# Main.net
KiCad netlist of a schematic drawn in Altium Designer
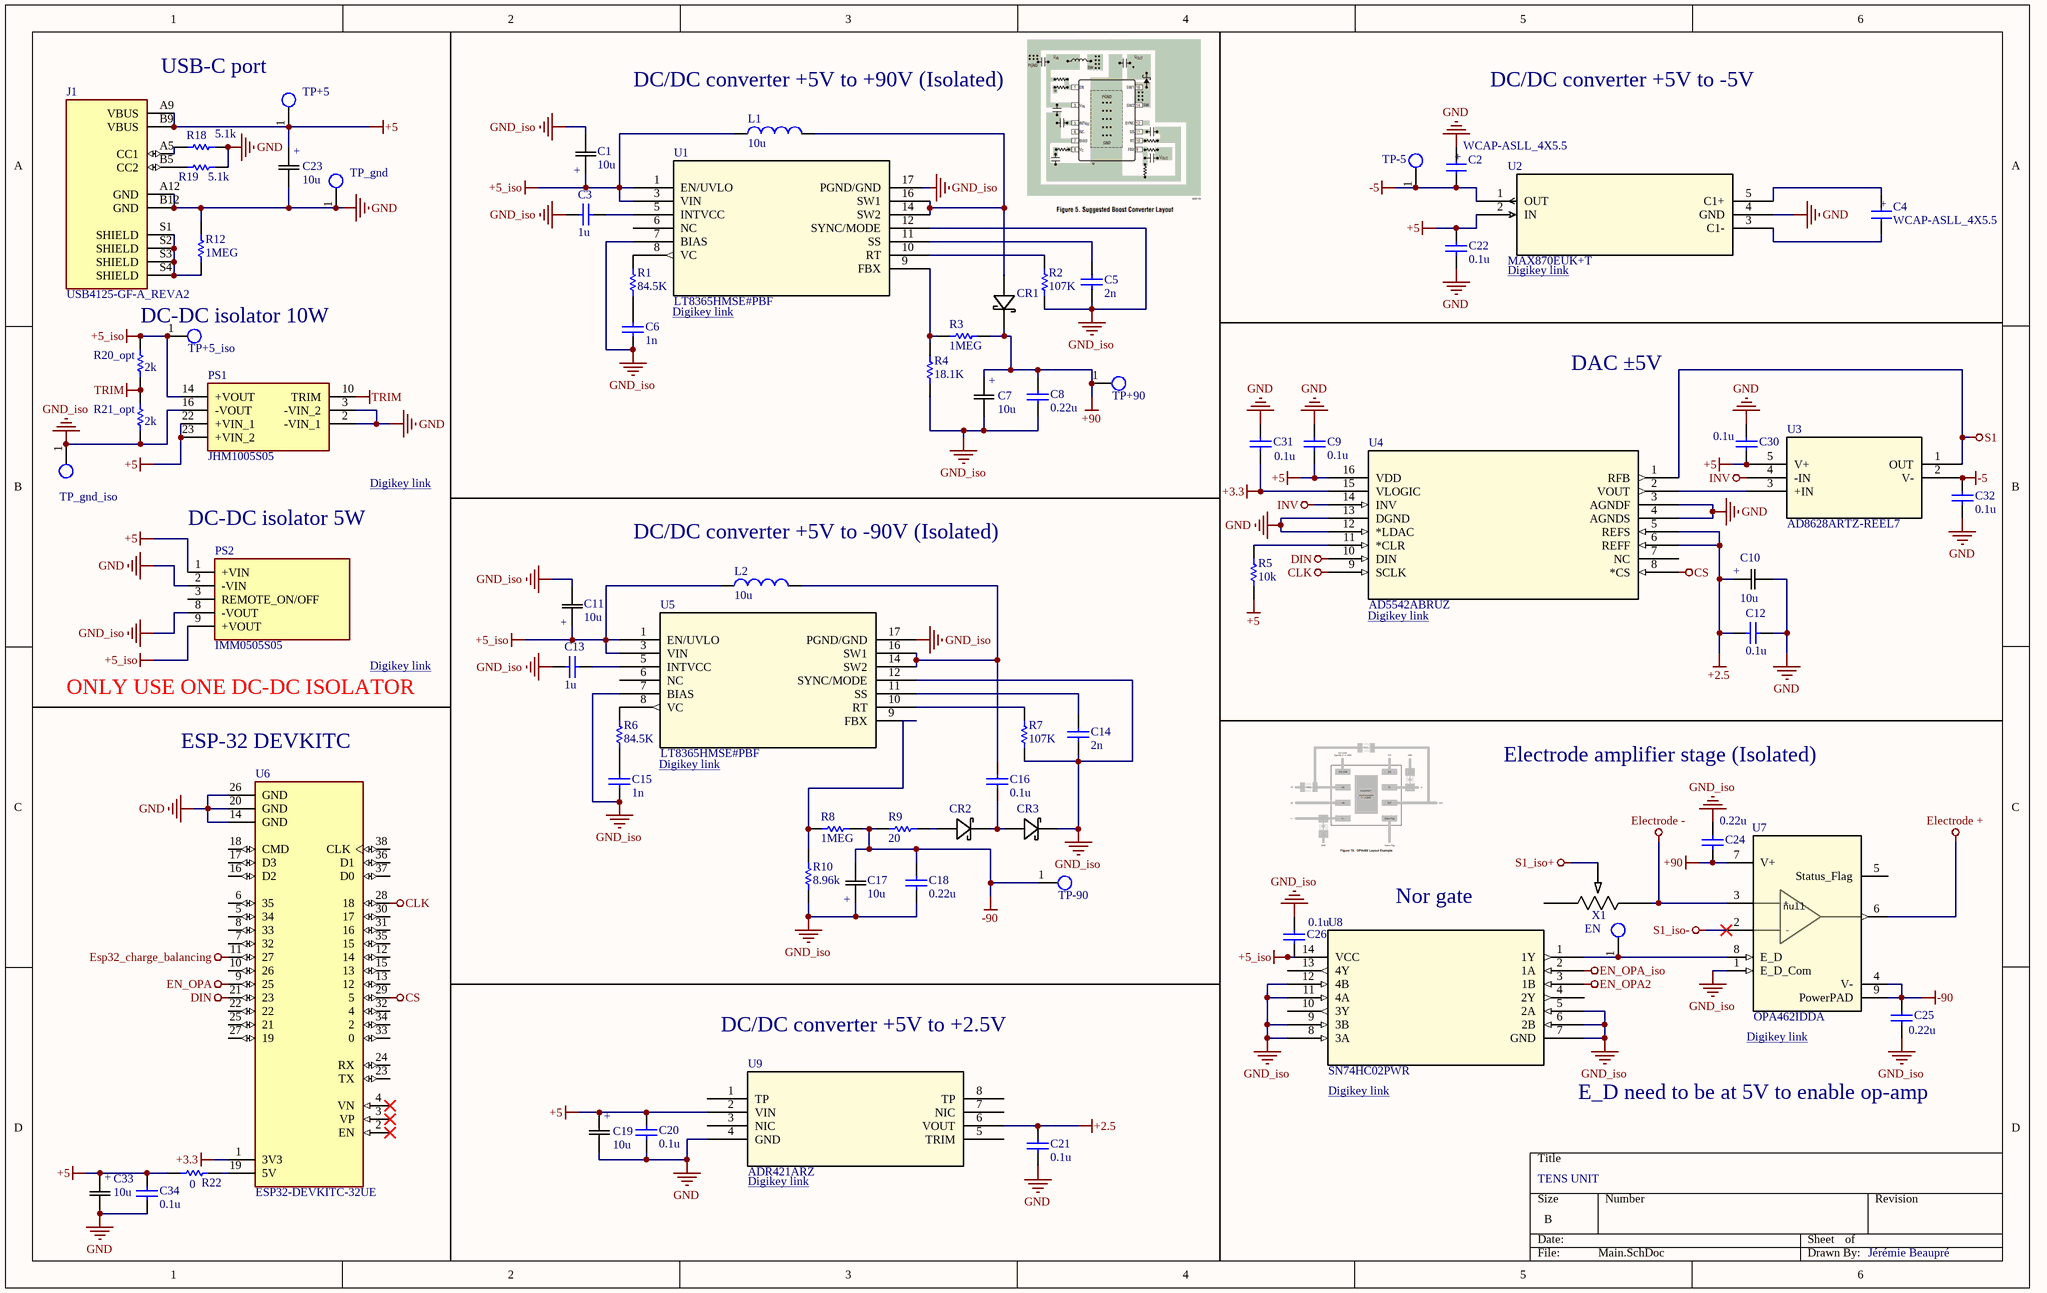
[diagram p0: Main.SchDoc]

(export (version "E")
  (design (tool "Eeschema 10.0.6"))
  (components
    (comp (ref "C1")
      (value "10u")
      (footprint "CAP_BX_10x20_RUB")
      (description "No Description Available")
      (fields
        (field (name "MANUFACTURER_PART_NUMBER") "450BXC10MEFC10X20")
        (field (name "COPYRIGHT") "Copyright (C) 2026 Ultra Librarian. All rights reserved.")
      )
      (libsource (lib "450BXC10MEFC10X20") (part "450BXC10MEFC10X20"))
    )
    (comp (ref "C2")
      (value "WCAP-ASLL_4X5.5")
      (footprint "WCAP-ASLL_4X5.5(DXL)")
      (fields
        (field (name "MF") "{'manufacturer': u'~{W}xfcrth Elektronik'}")
        (field (name "MP") "865060640001")
      )
      (libsource (lib "WCAP-ASLL_4X5.5") (part "WCAP-ASLL_4X5.5"))
    )
    (comp (ref "C3")
      (value "1u")
      (footprint "0805_AVX")
      (description "Capacitor")
      (libsource (lib "Simulation Generic Components") (part "Capacitor"))
    )
    (comp (ref "C4")
      (value "WCAP-ASLL_4X5.5")
      (footprint "WCAP-ASLL_4X5.5(DXL)")
      (fields
        (field (name "MF") "{'manufacturer': u'~{W}xfcrth Elektronik'}")
        (field (name "MP") "865060640001")
      )
      (libsource (lib "WCAP-ASLL_4X5.5") (part "WCAP-ASLL_4X5.5"))
    )
    (comp (ref "C5")
      (value "2n")
      (footprint "CAPC2012X75N")
      (description "Capacitor")
      (libsource (lib "Simulation Generic Components") (part "Capacitor"))
    )
    (comp (ref "C6")
      (value "1n")
      (footprint "CC0805N_YAG")
      (description "Capacitor")
      (libsource (lib "Simulation Generic Components") (part "Capacitor"))
    )
    (comp (ref "C7")
      (value "10u")
      (footprint "CAP_BX_10x20_RUB")
      (description "No Description Available")
      (fields
        (field (name "MANUFACTURER_PART_NUMBER") "450BXC10MEFC10X20")
        (field (name "COPYRIGHT") "Copyright (C) 2026 Ultra Librarian. All rights reserved.")
      )
      (libsource (lib "450BXC10MEFC10X20") (part "450BXC10MEFC10X20"))
    )
    (comp (ref "C8")
      (value "0.22u")
      (footprint "CAP_C3225X7R2E224K200AA")
      (description "Capacitor")
      (libsource (lib "Simulation Generic Components") (part "Capacitor"))
    )
    (comp (ref "C9")
      (value "0.1u")
      (footprint "CAPC2012X150N")
      (description "Capacitor")
      (libsource (lib "Simulation Generic Components") (part "Capacitor"))
    )
    (comp (ref "C10")
      (value "10u")
      (footprint "CAP_BX_10x20_RUB")
      (description "No Description Available")
      (fields
        (field (name "MANUFACTURER_PART_NUMBER") "450BXC10MEFC10X20")
        (field (name "COPYRIGHT") "Copyright (C) 2026 Ultra Librarian. All rights reserved.")
      )
      (libsource (lib "450BXC10MEFC10X20") (part "450BXC10MEFC10X20"))
    )
    (comp (ref "C11")
      (value "10u")
      (footprint "CAP_BX_10x20_RUB")
      (description "No Description Available")
      (fields
        (field (name "MANUFACTURER_PART_NUMBER") "450BXC10MEFC10X20")
        (field (name "COPYRIGHT") "Copyright (C) 2026 Ultra Librarian. All rights reserved.")
      )
      (libsource (lib "450BXC10MEFC10X20") (part "450BXC10MEFC10X20"))
    )
    (comp (ref "C12")
      (value "0.1u")
      (footprint "CAPC2012X150N")
      (description "Capacitor")
      (libsource (lib "Simulation Generic Components") (part "Capacitor"))
    )
    (comp (ref "C13")
      (value "1u")
      (footprint "0805_AVX")
      (description "Capacitor")
      (libsource (lib "Simulation Generic Components") (part "Capacitor"))
    )
    (comp (ref "C14")
      (value "2n")
      (footprint "CAPC2012X75N")
      (description "Capacitor")
      (libsource (lib "Simulation Generic Components") (part "Capacitor"))
    )
    (comp (ref "C15")
      (value "1n")
      (footprint "CC0805N_YAG")
      (description "Capacitor")
      (libsource (lib "Simulation Generic Components") (part "Capacitor"))
    )
    (comp (ref "C16")
      (value "0.1u")
      (footprint "CAPC2012X150N")
      (description "Capacitor")
      (libsource (lib "Simulation Generic Components") (part "Capacitor"))
    )
    (comp (ref "C17")
      (value "10u")
      (footprint "CAP_BX_10x20_RUB")
      (description "No Description Available")
      (fields
        (field (name "MANUFACTURER_PART_NUMBER") "450BXC10MEFC10X20")
        (field (name "COPYRIGHT") "Copyright (C) 2026 Ultra Librarian. All rights reserved.")
      )
      (libsource (lib "450BXC10MEFC10X20") (part "450BXC10MEFC10X20"))
    )
    (comp (ref "C18")
      (value "0.22u")
      (footprint "CAP_C3225X7R2E224K200AA")
      (description "Capacitor")
      (libsource (lib "Simulation Generic Components") (part "Capacitor"))
    )
    (comp (ref "C19")
      (value "10u")
      (footprint "CAP_BX_10x20_RUB")
      (description "No Description Available")
      (fields
        (field (name "MANUFACTURER_PART_NUMBER") "450BXC10MEFC10X20")
        (field (name "COPYRIGHT") "Copyright (C) 2026 Ultra Librarian. All rights reserved.")
      )
      (libsource (lib "450BXC10MEFC10X20") (part "450BXC10MEFC10X20"))
    )
    (comp (ref "C20")
      (value "0.1u")
      (footprint "CAPC2012X150N")
      (description "Capacitor")
      (libsource (lib "Simulation Generic Components") (part "Capacitor"))
    )
    (comp (ref "C21")
      (value "0.1u")
      (footprint "CAPC2012X150N")
      (description "Capacitor")
      (libsource (lib "Simulation Generic Components") (part "Capacitor"))
    )
    (comp (ref "C22")
      (value "0.1u")
      (footprint "CAPC2012X150N")
      (description "Capacitor")
      (libsource (lib "Simulation Generic Components") (part "Capacitor"))
    )
    (comp (ref "C23")
      (value "10u")
      (footprint "CAP_BX_10x20_RUB")
      (description "No Description Available")
      (fields
        (field (name "MANUFACTURER_PART_NUMBER") "450BXC10MEFC10X20")
        (field (name "COPYRIGHT") "Copyright (C) 2026 Ultra Librarian. All rights reserved.")
      )
      (libsource (lib "450BXC10MEFC10X20") (part "450BXC10MEFC10X20"))
    )
    (comp (ref "C24")
      (value "0.22u")
      (footprint "CAP_C3225X7R2E224K200AA")
      (description "Capacitor")
      (libsource (lib "Simulation Generic Components") (part "Capacitor"))
    )
    (comp (ref "C25")
      (value "0.22u")
      (footprint "CAP_C3225X7R2E224K200AA")
      (description "Capacitor")
      (libsource (lib "Simulation Generic Components") (part "Capacitor"))
    )
    (comp (ref "C26")
      (value "0.1u")
      (footprint "CAPC2012X150N")
      (description "Capacitor")
      (libsource (lib "Simulation Generic Components") (part "Capacitor"))
    )
    (comp (ref "C30")
      (value "0.1u")
      (footprint "CAPC2012X150N")
      (description "Capacitor")
      (libsource (lib "Simulation Generic Components") (part "Capacitor"))
    )
    (comp (ref "C31")
      (value "0.1u")
      (footprint "CAPC2012X150N")
      (description "Capacitor")
      (libsource (lib "Simulation Generic Components") (part "Capacitor"))
    )
    (comp (ref "C32")
      (value "0.1u")
      (footprint "CAPC2012X150N")
      (description "Capacitor")
      (libsource (lib "Simulation Generic Components") (part "Capacitor"))
    )
    (comp (ref "C33")
      (value "10u")
      (footprint "CAP_BX_10x20_RUB")
      (description "No Description Available")
      (fields
        (field (name "MANUFACTURER_PART_NUMBER") "450BXC10MEFC10X20")
        (field (name "COPYRIGHT") "Copyright (C) 2026 Ultra Librarian. All rights reserved.")
      )
      (libsource (lib "450BXC10MEFC10X20") (part "450BXC10MEFC10X20"))
    )
    (comp (ref "C34")
      (value "0.1u")
      (footprint "CAPC2012X150N")
      (description "Capacitor")
      (libsource (lib "Simulation Generic Components") (part "Capacitor"))
    )
    (comp (ref "CR1")
      (value "SK220ATR")
      (footprint "DIODE_SK220ATR_SMC-M")
      (description "No Description Available")
      (fields (field (name "COPYRIGHT") "Copyright (C) 2026 Ultra Librarian. All rights reserved."))
      (libsource (lib "SK220ATR") (part "SK220ATR"))
    )
    (comp (ref "CR2")
      (value "SK220ATR")
      (footprint "DIODE_SK220ATR_SMC-M")
      (description "No Description Available")
      (fields (field (name "COPYRIGHT") "Copyright (C) 2026 Ultra Librarian. All rights reserved."))
      (libsource (lib "SK220ATR") (part "SK220ATR"))
    )
    (comp (ref "CR3")
      (value "SK220ATR")
      (footprint "DIODE_SK220ATR_SMC-M")
      (description "No Description Available")
      (fields (field (name "COPYRIGHT") "Copyright (C) 2026 Ultra Librarian. All rights reserved."))
      (libsource (lib "SK220ATR") (part "SK220ATR"))
    )
    (comp (ref "EN")
      (value "Testpoint_1")
      (footprint "Testpoint1")
      (libsource (lib "My_lib") (part "Testpoint_1"))
    )
    (comp (ref "J1")
      (value "USB4125-GF-A_REVA2")
      (footprint "GCT_USB4125-GF-A_REVA2")
      (libsource (lib "USB4125-GF-A_REVA2") (part "USB4125-GF-A_REVA2"))
    )
    (comp (ref "L1")
      (value "10u")
      (footprint "DR73")
      (description "Inductor")
      (libsource (lib "Simulation Generic Components") (part "Inductor"))
    )
    (comp (ref "L2")
      (value "10u")
      (footprint "DR73")
      (description "Inductor")
      (libsource (lib "Simulation Generic Components") (part "Inductor"))
    )
    (comp (ref "PS1")
      (value "JHM1005S05")
      (footprint "SamacSys:JHM1005S05")
      (description "Power Supply")
      (fields (field (name "MOUSER PART NUMBER") "209-JHM1005S05"))
      (libsource (lib "*") (part "JHM1005S05"))
    )
    (comp (ref "PS2")
      (value "IMM0505S05")
      (footprint "SamacSys:IMM0505S05")
      (description "Power Supply")
      (fields (field (name "MOUSER PART NUMBER") "209-IMM0505S05"))
      (libsource (lib "*") (part "IMM0505S05"))
    )
    (comp (ref "R1")
      (value "84.5K")
      (footprint "Resistor_0805-M")
      (description "Resistor")
      (libsource (lib "Simulation Generic Components") (part "Resistor"))
    )
    (comp (ref "R2")
      (value "107K")
      (footprint "Resistor_0805-M")
      (description "Resistor")
      (libsource (lib "Simulation Generic Components") (part "Resistor"))
    )
    (comp (ref "R3")
      (value "1MEG")
      (footprint "Resistor_0805-M")
      (description "Resistor")
      (libsource (lib "Simulation Generic Components") (part "Resistor"))
    )
    (comp (ref "R4")
      (value "18.1K")
      (footprint "Resistor_0805-M")
      (description "Resistor")
      (libsource (lib "Simulation Generic Components") (part "Resistor"))
    )
    (comp (ref "R5")
      (value "10k")
      (footprint "Resistor_0805-M")
      (description "Resistor")
      (libsource (lib "Simulation Generic Components") (part "Resistor"))
    )
    (comp (ref "R6")
      (value "84.5K")
      (footprint "Resistor_0805-M")
      (description "Resistor")
      (libsource (lib "Simulation Generic Components") (part "Resistor"))
    )
    (comp (ref "R7")
      (value "107K")
      (footprint "Resistor_0805-M")
      (description "Resistor")
      (libsource (lib "Simulation Generic Components") (part "Resistor"))
    )
    (comp (ref "R8")
      (value "1MEG")
      (footprint "Resistor_0805-M")
      (description "Resistor")
      (libsource (lib "Simulation Generic Components") (part "Resistor"))
    )
    (comp (ref "R9")
      (value "20")
      (footprint "Resistor_0805-M")
      (description "Resistor")
      (libsource (lib "Simulation Generic Components") (part "Resistor"))
    )
    (comp (ref "R10")
      (value "8.96k")
      (footprint "Resistor_0805-M")
      (description "Resistor")
      (libsource (lib "Simulation Generic Components") (part "Resistor"))
    )
    (comp (ref "R12")
      (value "1MEG")
      (footprint "Resistor_0805-M")
      (description "Resistor")
      (libsource (lib "Simulation Generic Components") (part "Resistor"))
    )
    (comp (ref "R18")
      (value "5.1k")
      (footprint "Resistor_0805-M")
      (description "Resistor")
      (libsource (lib "Simulation Generic Components") (part "Resistor"))
    )
    (comp (ref "R19")
      (value "5.1k")
      (footprint "Resistor_0805-M")
      (description "Resistor")
      (libsource (lib "Simulation Generic Components") (part "Resistor"))
    )
    (comp (ref "R20_opt")
      (value "2k")
      (footprint "Resistor_0805-M")
      (description "Resistor")
      (libsource (lib "Simulation Generic Components") (part "Resistor"))
    )
    (comp (ref "R21_opt")
      (value "2k")
      (footprint "Resistor_0805-M")
      (description "Resistor")
      (libsource (lib "Simulation Generic Components") (part "Resistor"))
    )
    (comp (ref "R22")
      (value "0")
      (footprint "Resistor_0805-M")
      (description "Resistor")
      (libsource (lib "Simulation Generic Components") (part "Resistor"))
    )
    (comp (ref "TP+5")
      (value "Testpoint_1")
      (footprint "Testpoint1")
      (libsource (lib "My_lib") (part "Testpoint_1"))
    )
    (comp (ref "TP+5_iso")
      (value "Testpoint_1")
      (footprint "Testpoint1")
      (libsource (lib "My_lib") (part "Testpoint_1"))
    )
    (comp (ref "TP+90")
      (value "Testpoint_1")
      (footprint "Testpoint1")
      (libsource (lib "My_lib") (part "Testpoint_1"))
    )
    (comp (ref "TP-5")
      (value "Testpoint_1")
      (footprint "Testpoint1")
      (libsource (lib "My_lib") (part "Testpoint_1"))
    )
    (comp (ref "TP-90")
      (value "Testpoint_1")
      (footprint "Testpoint1")
      (libsource (lib "My_lib") (part "Testpoint_1"))
    )
    (comp (ref "TP_gnd")
      (value "Testpoint_1")
      (footprint "Testpoint1")
      (libsource (lib "My_lib") (part "Testpoint_1"))
    )
    (comp (ref "TP_gnd_iso")
      (value "Testpoint_1")
      (footprint "Testpoint1")
      (libsource (lib "My_lib") (part "Testpoint_1"))
    )
    (comp (ref "U1")
      (value "LT8365HMSE#PBF")
      (footprint "05-08-1871_ADI")
      (description "Low IQ Boost/SEPIC/Inverting Converter with 1.5A, 150V SwitchÂ")
      (fields (field (name "COPYRIGHT") "Copyright (C) 2025 Ultra Librarian. All rights reserved."))
      (libsource (lib "LT8365HMSEPBF") (part "LT8365HMSEPBF"))
    )
    (comp (ref "U2")
      (value "MAX870EUK+T")
      (footprint "21-0057F_MXM")
      (description "Switched-Capacitor Voltage Inverters")
      (fields (field (name "COPYRIGHT") "Copyright (C) 2026 Ultra Librarian. All rights reserved."))
      (libsource (lib "MAX870EUK&plus_T") (part "MAX870EUK+T"))
    )
    (comp (ref "U3")
      (value "AD8628ARTZ-REEL7")
      (footprint "RJ_5_ADI")
      (description "Zero-Drift, Single-Supply, Rail-to-Rail Input/Output Operational Amplifier")
      (fields (field (name "COPYRIGHT") "Copyright (C) 2025 Ultra Librarian. All rights reserved."))
      (libsource (lib "AD8628ARTZ-REEL7") (part "AD8628ARTZ-REEL7"))
    )
    (comp (ref "U4")
      (value "AD5542ABRUZ")
      (footprint "RU_16_ADI")
      (fields (field (name "COPYRIGHT") "Copyright (C) 2026 Ultra Librarian. All rights reserved."))
      (libsource (lib "AD5542ABRUZ") (part "AD5542ABRUZ"))
    )
    (comp (ref "U5")
      (value "LT8365HMSE#PBF")
      (footprint "05-08-1871_ADI")
      (description "Low IQ Boost/SEPIC/Inverting Converter with 1.5A, 150V SwitchÂ")
      (fields (field (name "COPYRIGHT") "Copyright (C) 2025 Ultra Librarian. All rights reserved."))
      (libsource (lib "LT8365HMSEPBF") (part "LT8365HMSEPBF"))
    )
    (comp (ref "U6")
      (value "ESP32-DEVKITC-32UE")
      (footprint "ESPRESSIF_ESP32-DEVKITC-32UE")
      (fields (field (name "MF") "Espressif Systems"))
      (libsource (lib "ESP32-DEVKITC-32UE") (part "ESP32-DEVKITC-32UE"))
    )
    (comp (ref "U7")
      (value "OPA462IDDA")
      (footprint "DDA0008J-IPC_A")
      (fields (field (name "COPYRIGHT") "Copyright (C) 2026 Ultra Librarian. All rights reserved."))
      (libsource (lib "OPA462IDDA") (part "OPA462IDDA"))
    )
    (comp (ref "U8")
      (value "SN74HC02PWR")
      (footprint "PW14")
      (description "4-ch, 2-input, 2-V to 6-V 5.2 mA drive strength NOR gate 14-TSSOP -40 to 85")
      (fields (field (name "COPYRIGHT") "Copyright (C) 2026 Ultra Librarian. All rights reserved."))
      (libsource (lib "SN74HC02PWR") (part "SN74HC02PWR"))
    )
    (comp (ref "U9")
      (value "ADR421ARZ")
      (footprint "R_8_ADI")
      (description "Ultraprecision, Low Noise, 2.500 V XFETÂ® Voltage References")
      (fields (field (name "COPYRIGHT") "Copyright (C) 2026 Ultra Librarian. All rights reserved."))
      (libsource (lib "ADR421ARZ") (part "ADR421ARZ"))
    )
    (comp (ref "X1")
      (value "PV36W102C01B00")
      (footprint "POT_PV36W_MUR")
      (description "No Description Available")
      (fields (field (name "COPYRIGHT") "Copyright (C) 2026 Ultra Librarian. All rights reserved."))
      (libsource (lib "PV36W102C01B00") (part "PV36W102C01B00"))
    )
  )
  (nets
    (net (code "1") (name "+2.5") (class "Default")
      (node (ref "C10") (pin "1") (pinfunction "+_1") (pintype "passive"))
      (node (ref "C12") (pin "2") (pinfunction "2_2") (pintype "passive"))
      (node (ref "C21") (pin "2") (pinfunction "2_2") (pintype "passive"))
      (node (ref "U4") (pin "5") (pinfunction "REFS_5") (pintype "input"))
      (node (ref "U4") (pin "6") (pinfunction "REFF_6") (pintype "input"))
      (node (ref "U9") (pin "6") (pinfunction "VOUT_6") (pintype "power_in"))
    )
    (net (code "2") (name "+3.3") (class "Default")
      (node (ref "C31") (pin "2") (pinfunction "2_2") (pintype "passive"))
      (node (ref "U4") (pin "15") (pinfunction "VLOGIC_15") (pintype "power_in"))
      (node (ref "U6") (pin "1") (pinfunction "3V3_1") (pintype "power_in"))
    )
    (net (code "3") (name "+5") (class "Default")
      (node (ref "C19") (pin "1") (pinfunction "+_1") (pintype "passive"))
      (node (ref "C20") (pin "2") (pinfunction "2_2") (pintype "passive"))
      (node (ref "C22") (pin "1") (pinfunction "1_1") (pintype "passive"))
      (node (ref "C23") (pin "1") (pinfunction "+_1") (pintype "passive"))
      (node (ref "C30") (pin "2") (pinfunction "2_2") (pintype "passive"))
      (node (ref "C33") (pin "1") (pinfunction "+_1") (pintype "passive"))
      (node (ref "C34") (pin "2") (pinfunction "2_2") (pintype "passive"))
      (node (ref "C9") (pin "2") (pinfunction "2_2") (pintype "passive"))
      (node (ref "J1") (pin "A9") (pinfunction "VBUS_A9") (pintype "power_in"))
      (node (ref "J1") (pin "B9") (pinfunction "VBUS_B9") (pintype "power_in"))
      (node (ref "PS1") (pin "22") (pinfunction "+VIN_1_22") (pintype "passive"))
      (node (ref "PS1") (pin "23") (pinfunction "+VIN_2_23") (pintype "passive"))
      (node (ref "PS2") (pin "1") (pinfunction "+VIN_1") (pintype "passive"))
      (node (ref "R22") (pin "2") (pinfunction "2_2") (pintype "passive"))
      (node (ref "R5") (pin "1") (pinfunction "1_1") (pintype "passive"))
      (node (ref "TP+5") (pin "1") (pinfunction "P1_1") (pintype "passive"))
      (node (ref "U2") (pin "2") (pinfunction "IN_2") (pintype "input"))
      (node (ref "U3") (pin "5") (pinfunction "V+_5") (pintype "power_in"))
      (node (ref "U4") (pin "16") (pinfunction "VDD_16") (pintype "power_in"))
      (node (ref "U9") (pin "2") (pinfunction "VIN_2") (pintype "passive"))
    )
    (net (code "4") (name "+5_iso") (class "Default")
      (node (ref "C1") (pin "1") (pinfunction "+_1") (pintype "passive"))
      (node (ref "C11") (pin "1") (pinfunction "+_1") (pintype "passive"))
      (node (ref "C26") (pin "1") (pinfunction "1_1") (pintype "passive"))
      (node (ref "L1") (pin "1") (pinfunction "1_1") (pintype "passive"))
      (node (ref "L2") (pin "1") (pinfunction "1_1") (pintype "passive"))
      (node (ref "PS1") (pin "14") (pinfunction "+VOUT_14") (pintype "passive"))
      (node (ref "PS2") (pin "9") (pinfunction "+VOUT_9") (pintype "passive"))
      (node (ref "R20_opt") (pin "1") (pinfunction "1_1") (pintype "passive"))
      (node (ref "TP+5_iso") (pin "1") (pinfunction "P1_1") (pintype "passive"))
      (node (ref "U1") (pin "1") (pinfunction "EN/UVLO_1") (pintype "passive"))
      (node (ref "U1") (pin "3") (pinfunction "VIN_3") (pintype "power_in"))
      (node (ref "U5") (pin "1") (pinfunction "EN/UVLO_1") (pintype "passive"))
      (node (ref "U5") (pin "3") (pinfunction "VIN_3") (pintype "power_in"))
      (node (ref "U8") (pin "14") (pinfunction "VCC_14") (pintype "power_in"))
    )
    (net (code "5") (name "+90") (class "Default")
      (node (ref "C24") (pin "2") (pinfunction "2_2") (pintype "passive"))
      (node (ref "C7") (pin "1") (pinfunction "+_1") (pintype "passive"))
      (node (ref "C8") (pin "2") (pinfunction "2_2") (pintype "passive"))
      (node (ref "CR1") (pin "1") (pinfunction "1_1") (pintype "passive"))
      (node (ref "R3") (pin "2") (pinfunction "2_2") (pintype "passive"))
      (node (ref "TP+90") (pin "1") (pinfunction "P1_1") (pintype "passive"))
      (node (ref "U7") (pin "7") (pinfunction "V+_7") (pintype "power_in"))
    )
    (net (code "6") (name "-5") (class "Default")
      (node (ref "C2") (pin "2") (pinfunction "NEG_2") (pintype "passive"))
      (node (ref "C32") (pin "2") (pinfunction "2_2") (pintype "passive"))
      (node (ref "TP-5") (pin "1") (pinfunction "P1_1") (pintype "passive"))
      (node (ref "U2") (pin "1") (pinfunction "OUT_1") (pintype "power_in"))
      (node (ref "U3") (pin "2") (pinfunction "V-_2") (pintype "power_in"))
    )
    (net (code "7") (name "-90") (class "Default")
      (node (ref "C17") (pin "2") (pinfunction "2_2") (pintype "passive"))
      (node (ref "C18") (pin "2") (pinfunction "2_2") (pintype "passive"))
      (node (ref "C25") (pin "1") (pinfunction "1_1") (pintype "passive"))
      (node (ref "R8") (pin "1") (pinfunction "1_1") (pintype "passive"))
      (node (ref "R9") (pin "2") (pinfunction "2_2") (pintype "passive"))
      (node (ref "TP-90") (pin "1") (pinfunction "P1_1") (pintype "passive"))
      (node (ref "U7") (pin "4") (pinfunction "V-_4") (pintype "power_in"))
      (node (ref "U7") (pin "9") (pinfunction "PowerPAD_9") (pintype "power_in"))
    )
    (net (code "8") (name "CLK") (class "Default")
      (node (ref "U4") (pin "9") (pinfunction "SCLK_9") (pintype "input"))
      (node (ref "U6") (pin "28") (pinfunction "18_28") (pintype "bidirectional"))
    )
    (net (code "9") (name "CS") (class "Default")
      (node (ref "U4") (pin "8") (pinfunction "*CS_8") (pintype "input"))
      (node (ref "U6") (pin "29") (pinfunction "5_29") (pintype "bidirectional"))
    )
    (net (code "10") (name "DIN") (class "Default")
      (node (ref "U4") (pin "10") (pinfunction "DIN_10") (pintype "input"))
      (node (ref "U6") (pin "21") (pinfunction "23_21") (pintype "bidirectional"))
    )
    (net (code "11") (name "EN_OPA") (class "Default")
      (node (ref "U6") (pin "9") (pinfunction "25_9") (pintype "bidirectional"))
    )
    (net (code "12") (name "EN_OPA2") (class "Default")
      (node (ref "U8") (pin "3") (pinfunction "1B_3") (pintype "input"))
    )
    (net (code "13") (name "EN_OPA_iso") (class "Default")
      (node (ref "U8") (pin "2") (pinfunction "1A_2") (pintype "input"))
    )
    (net (code "14") (name "Electrode +") (class "Default")
      (node (ref "U7") (pin "6") (pinfunction "OUT_6") (pintype "output"))
    )
    (net (code "15") (name "Electrode -") (class "Default")
      (node (ref "U7") (pin "3") (pinfunction "+IN_3") (pintype "tri_state"))
      (node (ref "X1") (pin "3") (pinfunction "3_3") (pintype "passive"))
    )
    (net (code "16") (name "Esp32_charge_balancing") (class "Default")
      (node (ref "U6") (pin "11") (pinfunction "27_11") (pintype "bidirectional"))
    )
    (net (code "17") (name "GND") (class "Default")
      (node (ref "C10") (pin "2") (pinfunction "2_2") (pintype "passive"))
      (node (ref "C12") (pin "1") (pinfunction "1_1") (pintype "passive"))
      (node (ref "C19") (pin "2") (pinfunction "2_2") (pintype "passive"))
      (node (ref "C2") (pin "1") (pinfunction "POS_1") (pintype "passive"))
      (node (ref "C20") (pin "1") (pinfunction "1_1") (pintype "passive"))
      (node (ref "C21") (pin "1") (pinfunction "1_1") (pintype "passive"))
      (node (ref "C22") (pin "2") (pinfunction "2_2") (pintype "passive"))
      (node (ref "C23") (pin "2") (pinfunction "2_2") (pintype "passive"))
      (node (ref "C30") (pin "1") (pinfunction "1_1") (pintype "passive"))
      (node (ref "C31") (pin "1") (pinfunction "1_1") (pintype "passive"))
      (node (ref "C32") (pin "1") (pinfunction "1_1") (pintype "passive"))
      (node (ref "C33") (pin "2") (pinfunction "2_2") (pintype "passive"))
      (node (ref "C34") (pin "1") (pinfunction "1_1") (pintype "passive"))
      (node (ref "C9") (pin "1") (pinfunction "1_1") (pintype "passive"))
      (node (ref "J1") (pin "A12") (pinfunction "GND_A12") (pintype "power_in"))
      (node (ref "J1") (pin "B12") (pinfunction "GND_B12") (pintype "power_in"))
      (node (ref "PS1") (pin "2") (pinfunction "-VIN_1_2") (pintype "passive"))
      (node (ref "PS1") (pin "3") (pinfunction "-VIN_2_3") (pintype "passive"))
      (node (ref "PS2") (pin "2") (pinfunction "-VIN_2") (pintype "passive"))
      (node (ref "R12") (pin "2") (pinfunction "2_2") (pintype "passive"))
      (node (ref "R18") (pin "1") (pinfunction "1_1") (pintype "passive"))
      (node (ref "R19") (pin "1") (pinfunction "1_1") (pintype "passive"))
      (node (ref "TP_gnd") (pin "1") (pinfunction "P1_1") (pintype "passive"))
      (node (ref "U2") (pin "4") (pinfunction "GND_4") (pintype "power_in"))
      (node (ref "U4") (pin "12") (pinfunction "*LDAC_12") (pintype "input"))
      (node (ref "U4") (pin "13") (pinfunction "DGND_13") (pintype "power_in"))
      (node (ref "U4") (pin "3") (pinfunction "AGNDF_3") (pintype "power_in"))
      (node (ref "U4") (pin "4") (pinfunction "AGNDS_4") (pintype "power_in"))
      (node (ref "U6") (pin "14") (pinfunction "GND_14") (pintype "power_in"))
      (node (ref "U6") (pin "20") (pinfunction "GND_20") (pintype "power_in"))
      (node (ref "U6") (pin "26") (pinfunction "GND_26") (pintype "power_in"))
      (node (ref "U9") (pin "4") (pinfunction "GND_4") (pintype "passive"))
    )
    (net (code "18") (name "GND_iso") (class "Default")
      (node (ref "C1") (pin "2") (pinfunction "2_2") (pintype "passive"))
      (node (ref "C11") (pin "2") (pinfunction "2_2") (pintype "passive"))
      (node (ref "C13") (pin "2") (pinfunction "2_2") (pintype "passive"))
      (node (ref "C14") (pin "1") (pinfunction "1_1") (pintype "passive"))
      (node (ref "C15") (pin "1") (pinfunction "1_1") (pintype "passive"))
      (node (ref "C17") (pin "1") (pinfunction "+_1") (pintype "passive"))
      (node (ref "C18") (pin "1") (pinfunction "1_1") (pintype "passive"))
      (node (ref "C24") (pin "1") (pinfunction "1_1") (pintype "passive"))
      (node (ref "C25") (pin "2") (pinfunction "2_2") (pintype "passive"))
      (node (ref "C26") (pin "2") (pinfunction "2_2") (pintype "passive"))
      (node (ref "C3") (pin "2") (pinfunction "2_2") (pintype "passive"))
      (node (ref "C5") (pin "1") (pinfunction "1_1") (pintype "passive"))
      (node (ref "C6") (pin "1") (pinfunction "1_1") (pintype "passive"))
      (node (ref "C7") (pin "2") (pinfunction "2_2") (pintype "passive"))
      (node (ref "C8") (pin "1") (pinfunction "1_1") (pintype "passive"))
      (node (ref "CR3") (pin "1") (pinfunction "1_1") (pintype "passive"))
      (node (ref "PS1") (pin "16") (pinfunction "-VOUT_16") (pintype "passive"))
      (node (ref "PS2") (pin "8") (pinfunction "-VOUT_8") (pintype "passive"))
      (node (ref "R10") (pin "2") (pinfunction "2_2") (pintype "passive"))
      (node (ref "R2") (pin "1") (pinfunction "1_1") (pintype "passive"))
      (node (ref "R21_opt") (pin "2") (pinfunction "2_2") (pintype "passive"))
      (node (ref "R4") (pin "2") (pinfunction "2_2") (pintype "passive"))
      (node (ref "R7") (pin "1") (pinfunction "1_1") (pintype "passive"))
      (node (ref "TP_gnd_iso") (pin "1") (pinfunction "P1_1") (pintype "passive"))
      (node (ref "U1") (pin "12") (pinfunction "SYNC/MODE_12") (pintype "passive"))
      (node (ref "U1") (pin "17") (pinfunction "PGND/GND_17") (pintype "power_in"))
      (node (ref "U1") (pin "7") (pinfunction "BIAS_7") (pintype "power_in"))
      (node (ref "U5") (pin "12") (pinfunction "SYNC/MODE_12") (pintype "passive"))
      (node (ref "U5") (pin "17") (pinfunction "PGND/GND_17") (pintype "power_in"))
      (node (ref "U5") (pin "7") (pinfunction "BIAS_7") (pintype "power_in"))
      (node (ref "U7") (pin "1") (pinfunction "E_D_Com_1") (pintype "input"))
      (node (ref "U8") (pin "11") (pinfunction "4A_11") (pintype "input"))
      (node (ref "U8") (pin "12") (pinfunction "4B_12") (pintype "input"))
      (node (ref "U8") (pin "5") (pinfunction "2A_5") (pintype "input"))
      (node (ref "U8") (pin "6") (pinfunction "2B_6") (pintype "input"))
      (node (ref "U8") (pin "7") (pinfunction "GND_7") (pintype "power_in"))
      (node (ref "U8") (pin "8") (pinfunction "3A_8") (pintype "input"))
      (node (ref "U8") (pin "9") (pinfunction "3B_9") (pintype "input"))
    )
    (net (code "19") (name "INV") (class "Default")
      (node (ref "U3") (pin "4") (pinfunction "-IN_4") (pintype "passive"))
      (node (ref "U4") (pin "14") (pinfunction "INV_14") (pintype "input"))
    )
    (net (code "20") (name "Net-(C4-NEG)") (class "Default")
      (node (ref "C4") (pin "2") (pinfunction "NEG_2") (pintype "passive"))
      (node (ref "U2") (pin "3") (pinfunction "C1-_3") (pintype "passive"))
    )
    (net (code "21") (name "Net-(C4-POS)") (class "Default")
      (node (ref "C4") (pin "1") (pinfunction "POS_1") (pintype "passive"))
      (node (ref "U2") (pin "5") (pinfunction "C1+_5") (pintype "passive"))
    )
    (net (code "22") (name "Net-(C6-Pad2)") (class "Default")
      (node (ref "C6") (pin "2") (pinfunction "2_2") (pintype "passive"))
      (node (ref "R1") (pin "1") (pinfunction "1_1") (pintype "passive"))
    )
    (net (code "23") (name "Net-(C15-Pad2)") (class "Default")
      (node (ref "C15") (pin "2") (pinfunction "2_2") (pintype "passive"))
      (node (ref "R6") (pin "1") (pinfunction "1_1") (pintype "passive"))
    )
    (net (code "24") (name "Net-(C16-Pad1)") (class "Default")
      (node (ref "C16") (pin "1") (pinfunction "1_1") (pintype "passive"))
      (node (ref "CR2") (pin "1") (pinfunction "1_1") (pintype "passive"))
      (node (ref "CR3") (pin "2") (pinfunction "2_2") (pintype "passive"))
    )
    (net (code "25") (name "Net-(CR2-Pad2)") (class "Default")
      (node (ref "CR2") (pin "2") (pinfunction "2_2") (pintype "passive"))
      (node (ref "R9") (pin "1") (pinfunction "1_1") (pintype "passive"))
    )
    (net (code "26") (name "Net-(EN-P1)") (class "Default")
      (node (ref "EN") (pin "1") (pinfunction "P1_1") (pintype "passive"))
      (node (ref "U7") (pin "8") (pinfunction "E_D_8") (pintype "input"))
      (node (ref "U8") (pin "1") (pinfunction "1Y_1") (pintype "output"))
    )
    (net (code "27") (name "Net-(J1-CC1)") (class "Default")
      (node (ref "J1") (pin "A5") (pinfunction "CC1_A5") (pintype "bidirectional"))
      (node (ref "R18") (pin "2") (pinfunction "2_2") (pintype "passive"))
    )
    (net (code "28") (name "Net-(J1-CC2)") (class "Default")
      (node (ref "J1") (pin "B5") (pinfunction "CC2_B5") (pintype "bidirectional"))
      (node (ref "R19") (pin "2") (pinfunction "2_2") (pintype "passive"))
    )
    (net (code "29") (name "Net-(J1-SHIELD-PadS1)") (class "Default")
      (node (ref "J1") (pin "S1") (pinfunction "SHIELD_S1") (pintype "passive"))
      (node (ref "J1") (pin "S2") (pinfunction "SHIELD_S2") (pintype "passive"))
      (node (ref "J1") (pin "S3") (pinfunction "SHIELD_S3") (pintype "passive"))
      (node (ref "J1") (pin "S4") (pinfunction "SHIELD_S4") (pintype "passive"))
      (node (ref "R12") (pin "1") (pinfunction "1_1") (pintype "passive"))
    )
    (net (code "30") (name "Net-(U1-FBX)") (class "Default")
      (node (ref "R3") (pin "1") (pinfunction "1_1") (pintype "passive"))
      (node (ref "R4") (pin "1") (pinfunction "1_1") (pintype "passive"))
      (node (ref "U1") (pin "9") (pinfunction "FBX_9") (pintype "passive"))
    )
    (net (code "31") (name "Net-(U1-INTVCC)") (class "Default")
      (node (ref "C3") (pin "1") (pinfunction "1_1") (pintype "passive"))
      (node (ref "U1") (pin "5") (pinfunction "INTVCC_5") (pintype "power_in"))
    )
    (net (code "32") (name "Net-(U1-RT)") (class "Default")
      (node (ref "R2") (pin "2") (pinfunction "2_2") (pintype "passive"))
      (node (ref "U1") (pin "10") (pinfunction "RT_10") (pintype "passive"))
    )
    (net (code "33") (name "Net-(U1-SS)") (class "Default")
      (node (ref "C5") (pin "2") (pinfunction "2_2") (pintype "passive"))
      (node (ref "U1") (pin "11") (pinfunction "SS_11") (pintype "passive"))
    )
    (net (code "34") (name "Net-(U1-SW1)") (class "Default")
      (node (ref "CR1") (pin "2") (pinfunction "2_2") (pintype "passive"))
      (node (ref "L1") (pin "2") (pinfunction "2_2") (pintype "passive"))
      (node (ref "U1") (pin "14") (pinfunction "SW2_14") (pintype "power_in"))
      (node (ref "U1") (pin "16") (pinfunction "SW1_16") (pintype "power_in"))
    )
    (net (code "35") (name "Net-(U1-VC)") (class "Default")
      (node (ref "R1") (pin "2") (pinfunction "2_2") (pintype "passive"))
      (node (ref "U1") (pin "8") (pinfunction "VC_8") (pintype "output"))
    )
    (net (code "36") (name "Net-(U3-+IN)") (class "Default")
      (node (ref "U3") (pin "3") (pinfunction "+IN_3") (pintype "passive"))
      (node (ref "U4") (pin "2") (pinfunction "VOUT_2") (pintype "output"))
    )
    (net (code "37") (name "Net-(U4-*CLR)") (class "Default")
      (node (ref "R5") (pin "2") (pinfunction "2_2") (pintype "passive"))
      (node (ref "U4") (pin "11") (pinfunction "*CLR_11") (pintype "input"))
    )
    (net (code "38") (name "Net-(U5-FBX)") (class "Default")
      (node (ref "R10") (pin "1") (pinfunction "1_1") (pintype "passive"))
      (node (ref "R8") (pin "2") (pinfunction "2_2") (pintype "passive"))
      (node (ref "U5") (pin "9") (pinfunction "FBX_9") (pintype "passive"))
    )
    (net (code "39") (name "Net-(U5-INTVCC)") (class "Default")
      (node (ref "C13") (pin "1") (pinfunction "1_1") (pintype "passive"))
      (node (ref "U5") (pin "5") (pinfunction "INTVCC_5") (pintype "power_in"))
    )
    (net (code "40") (name "Net-(U5-RT)") (class "Default")
      (node (ref "R7") (pin "2") (pinfunction "2_2") (pintype "passive"))
      (node (ref "U5") (pin "10") (pinfunction "RT_10") (pintype "passive"))
    )
    (net (code "41") (name "Net-(U5-SS)") (class "Default")
      (node (ref "C14") (pin "2") (pinfunction "2_2") (pintype "passive"))
      (node (ref "U5") (pin "11") (pinfunction "SS_11") (pintype "passive"))
    )
    (net (code "42") (name "Net-(U5-SW1)") (class "Default")
      (node (ref "C16") (pin "2") (pinfunction "2_2") (pintype "passive"))
      (node (ref "L2") (pin "2") (pinfunction "2_2") (pintype "passive"))
      (node (ref "U5") (pin "14") (pinfunction "SW2_14") (pintype "power_in"))
      (node (ref "U5") (pin "16") (pinfunction "SW1_16") (pintype "power_in"))
    )
    (net (code "43") (name "Net-(U5-VC)") (class "Default")
      (node (ref "R6") (pin "2") (pinfunction "2_2") (pintype "passive"))
      (node (ref "U5") (pin "8") (pinfunction "VC_8") (pintype "output"))
    )
    (net (code "44") (name "Net-(U6-5V)") (class "Default")
      (node (ref "R22") (pin "1") (pinfunction "1_1") (pintype "passive"))
      (node (ref "U6") (pin "19") (pinfunction "5V_19") (pintype "power_in"))
    )
    (net (code "45") (name "S1") (class "Default")
      (node (ref "U3") (pin "1") (pinfunction "OUT_1") (pintype "passive"))
      (node (ref "U4") (pin "1") (pinfunction "RFB_1") (pintype "output"))
    )
    (net (code "46") (name "S1_iso+") (class "Default")
      (node (ref "X1") (pin "2") (pinfunction "2_2") (pintype "passive"))
    )
    (net (code "47") (name "S1_iso-") (class "Default")
      (node (ref "U7") (pin "2") (pinfunction "-IN_2") (pintype "tri_state"))
    )
    (net (code "48") (name "TRIM") (class "Default")
      (node (ref "PS1") (pin "10") (pinfunction "TRIM_10") (pintype "passive"))
      (node (ref "R20_opt") (pin "2") (pinfunction "2_2") (pintype "passive"))
      (node (ref "R21_opt") (pin "1") (pinfunction "1_1") (pintype "passive"))
    )
    (net (code "49") (name "unconnected-(PS2-REMOTE_ON{slash}OFF-Pad3)") (class "Default")
      (node (ref "PS2") (pin "3") (pinfunction "REMOTE_ON/OFF_3") (pintype "passive"))
    )
    (net (code "50") (name "unconnected-(U1-NC-Pad6)") (class "Default")
      (node (ref "U1") (pin "6") (pinfunction "NC_6") (pintype "passive"))
    )
    (net (code "51") (name "unconnected-(U4-NC-Pad7)") (class "Default")
      (node (ref "U4") (pin "7") (pinfunction "NC_7") (pintype "passive"))
    )
    (net (code "52") (name "unconnected-(U5-NC-Pad6)") (class "Default")
      (node (ref "U5") (pin "6") (pinfunction "NC_6") (pintype "passive"))
    )
    (net (code "53") (name "unconnected-(U6-0-Pad33)") (class "Default")
      (node (ref "U6") (pin "33") (pinfunction "0_33") (pintype "bidirectional"))
    )
    (net (code "54") (name "unconnected-(U6-2-Pad34)") (class "Default")
      (node (ref "U6") (pin "34") (pinfunction "2_34") (pintype "bidirectional"))
    )
    (net (code "55") (name "unconnected-(U6-4-Pad32)") (class "Default")
      (node (ref "U6") (pin "32") (pinfunction "4_32") (pintype "bidirectional"))
    )
    (net (code "56") (name "unconnected-(U6-12-Pad13)") (class "Default")
      (node (ref "U6") (pin "13") (pinfunction "12_13") (pintype "bidirectional"))
    )
    (net (code "57") (name "unconnected-(U6-13-Pad15)") (class "Default")
      (node (ref "U6") (pin "15") (pinfunction "13_15") (pintype "bidirectional"))
    )
    (net (code "58") (name "unconnected-(U6-14-Pad12)") (class "Default")
      (node (ref "U6") (pin "12") (pinfunction "14_12") (pintype "bidirectional"))
    )
    (net (code "59") (name "unconnected-(U6-15-Pad35)") (class "Default")
      (node (ref "U6") (pin "35") (pinfunction "15_35") (pintype "bidirectional"))
    )
    (net (code "60") (name "unconnected-(U6-16-Pad31)") (class "Default")
      (node (ref "U6") (pin "31") (pinfunction "16_31") (pintype "bidirectional"))
    )
    (net (code "61") (name "unconnected-(U6-17-Pad30)") (class "Default")
      (node (ref "U6") (pin "30") (pinfunction "17_30") (pintype "bidirectional"))
    )
    (net (code "62") (name "unconnected-(U6-19-Pad27)") (class "Default")
      (node (ref "U6") (pin "27") (pinfunction "19_27") (pintype "bidirectional"))
    )
    (net (code "63") (name "unconnected-(U6-21-Pad25)") (class "Default")
      (node (ref "U6") (pin "25") (pinfunction "21_25") (pintype "bidirectional"))
    )
    (net (code "64") (name "unconnected-(U6-26-Pad10)") (class "Default")
      (node (ref "U6") (pin "10") (pinfunction "26_10") (pintype "bidirectional"))
    )
    (net (code "65") (name "unconnected-(U6-32-Pad7)") (class "Default")
      (node (ref "U6") (pin "7") (pinfunction "32_7") (pintype "bidirectional"))
    )
    (net (code "66") (name "unconnected-(U6-33-Pad8)") (class "Default")
      (node (ref "U6") (pin "8") (pinfunction "33_8") (pintype "bidirectional"))
    )
    (net (code "67") (name "unconnected-(U6-34-Pad5)") (class "Default")
      (node (ref "U6") (pin "5") (pinfunction "34_5") (pintype "bidirectional"))
    )
    (net (code "68") (name "unconnected-(U6-35-Pad6)") (class "Default")
      (node (ref "U6") (pin "6") (pinfunction "35_6") (pintype "bidirectional"))
    )
    (net (code "69") (name "unconnected-(U6-CLK-Pad38)") (class "Default")
      (node (ref "U6") (pin "38") (pinfunction "CLK_38") (pintype "bidirectional"))
    )
    (net (code "70") (name "unconnected-(U6-CMD-Pad18)") (class "Default")
      (node (ref "U6") (pin "18") (pinfunction "CMD_18") (pintype "bidirectional"))
    )
    (net (code "71") (name "unconnected-(U6-D0-Pad37)") (class "Default")
      (node (ref "U6") (pin "37") (pinfunction "D0_37") (pintype "bidirectional"))
    )
    (net (code "72") (name "unconnected-(U6-D1-Pad36)") (class "Default")
      (node (ref "U6") (pin "36") (pinfunction "D1_36") (pintype "bidirectional"))
    )
    (net (code "73") (name "unconnected-(U6-D2-Pad16)") (class "Default")
      (node (ref "U6") (pin "16") (pinfunction "D2_16") (pintype "bidirectional"))
    )
    (net (code "74") (name "unconnected-(U6-D3-Pad17)") (class "Default")
      (node (ref "U6") (pin "17") (pinfunction "D3_17") (pintype "bidirectional"))
    )
    (net (code "75") (name "unconnected-(U6-EN-Pad2)") (class "Default")
      (node (ref "U6") (pin "2") (pinfunction "EN_2") (pintype "input+no_connect"))
    )
    (net (code "76") (name "unconnected-(U6-Pad22)") (class "Default")
      (node (ref "U6") (pin "22") (pinfunction "22_22") (pintype "bidirectional"))
    )
    (net (code "77") (name "unconnected-(U6-RX-Pad24)") (class "Default")
      (node (ref "U6") (pin "24") (pinfunction "RX_24") (pintype "bidirectional"))
    )
    (net (code "78") (name "unconnected-(U6-TX-Pad23)") (class "Default")
      (node (ref "U6") (pin "23") (pinfunction "TX_23") (pintype "bidirectional"))
    )
    (net (code "79") (name "unconnected-(U6-VN-Pad4)") (class "Default")
      (node (ref "U6") (pin "4") (pinfunction "VN_4") (pintype "input+no_connect"))
    )
    (net (code "80") (name "unconnected-(U6-VP-Pad3)") (class "Default")
      (node (ref "U6") (pin "3") (pinfunction "VP_3") (pintype "input+no_connect"))
    )
    (net (code "81") (name "unconnected-(U7-Status_Flag-Pad5)") (class "Default")
      (node (ref "U7") (pin "5") (pinfunction "Status_Flag_5") (pintype "open_collector"))
    )
    (net (code "82") (name "unconnected-(U8-2Y-Pad4)") (class "Default")
      (node (ref "U8") (pin "4") (pinfunction "2Y_4") (pintype "output"))
    )
    (net (code "83") (name "unconnected-(U8-3Y-Pad10)") (class "Default")
      (node (ref "U8") (pin "10") (pinfunction "3Y_10") (pintype "output"))
    )
    (net (code "84") (name "unconnected-(U8-4Y-Pad13)") (class "Default")
      (node (ref "U8") (pin "13") (pinfunction "4Y_13") (pintype "output"))
    )
    (net (code "85") (name "unconnected-(U9-NIC-Pad3)") (class "Default")
      (node (ref "U9") (pin "3") (pinfunction "NIC_3") (pintype "passive"))
    )
    (net (code "86") (name "unconnected-(U9-NIC-Pad7)") (class "Default")
      (node (ref "U9") (pin "7") (pinfunction "NIC_7") (pintype "passive"))
    )
    (net (code "87") (name "unconnected-(U9-TP-Pad1)") (class "Default")
      (node (ref "U9") (pin "1") (pinfunction "TP_1") (pintype "passive"))
    )
    (net (code "88") (name "unconnected-(U9-TP-Pad8)") (class "Default")
      (node (ref "U9") (pin "8") (pinfunction "TP_8") (pintype "passive"))
    )
    (net (code "89") (name "unconnected-(U9-TRIM-Pad5)") (class "Default")
      (node (ref "U9") (pin "5") (pinfunction "TRIM_5") (pintype "passive"))
    )
    (net (code "90") (name "unconnected-(X1-Pad1)") (class "Default")
      (node (ref "X1") (pin "1") (pinfunction "1_1") (pintype "passive"))
    )
  )
)
